# power_cleanup.net
KiCad netlist of a schematic drawn in EAGLE
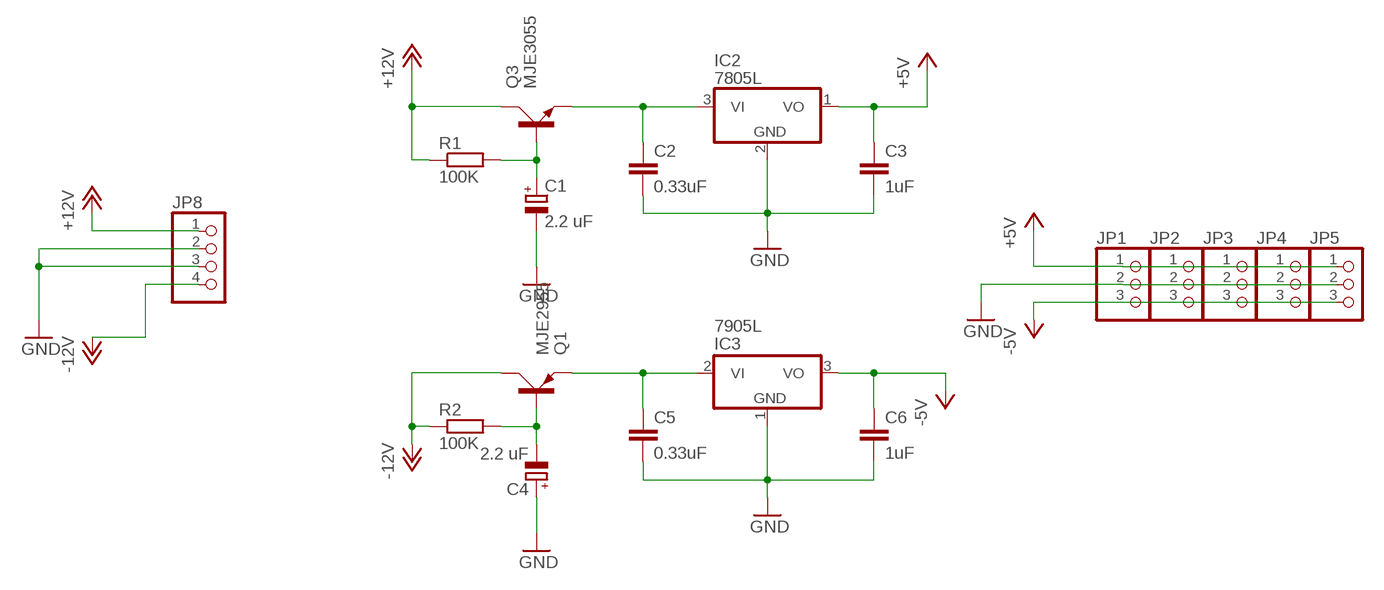
[diagram p0: schematic, sheet 1]

(export (version "E")
  (design (tool "Eeschema 10.0.6"))
  (components
    (comp (ref "C1")
      (value "2.2 uF")
      (footprint "eagle-import:E2-5")
      (libsource (lib "eagle-import") (part "CPOL-EUE2-5"))
    )
    (comp (ref "C2")
      (value "0.33uF")
      (footprint "eagle-import:C025-025X050")
      (libsource (lib "eagle-import") (part "C-EU025-025X050"))
    )
    (comp (ref "C3")
      (value "1uF")
      (footprint "eagle-import:C025-025X050")
      (libsource (lib "eagle-import") (part "C-EU025-025X050"))
    )
    (comp (ref "C4")
      (value "2.2 uF")
      (footprint "eagle-import:E2-5")
      (libsource (lib "eagle-import") (part "CPOL-EUE2-5"))
    )
    (comp (ref "C5")
      (value "0.33uF")
      (footprint "eagle-import:C025-025X050")
      (libsource (lib "eagle-import") (part "C-EU025-025X050"))
    )
    (comp (ref "C6")
      (value "1uF")
      (footprint "eagle-import:C025-025X050")
      (libsource (lib "eagle-import") (part "C-EU025-025X050"))
    )
    (comp (ref "IC2")
      (value "7805L")
      (footprint "eagle-import:TO92")
      (libsource (lib "eagle-import") (part "78L05"))
    )
    (comp (ref "IC3")
      (value "7905L")
      (footprint "eagle-import:TO92")
      (libsource (lib "eagle-import") (part "79L05"))
    )
    (comp (ref "JP1")
      (value "PINHD-1X3")
      (footprint "eagle-import:1X03")
      (libsource (lib "eagle-import") (part "PINHD-1X3"))
    )
    (comp (ref "JP2")
      (value "PINHD-1X3")
      (footprint "eagle-import:1X03")
      (libsource (lib "eagle-import") (part "PINHD-1X3"))
    )
    (comp (ref "JP3")
      (value "PINHD-1X3")
      (footprint "eagle-import:1X03")
      (libsource (lib "eagle-import") (part "PINHD-1X3"))
    )
    (comp (ref "JP4")
      (value "PINHD-1X3")
      (footprint "eagle-import:1X03")
      (libsource (lib "eagle-import") (part "PINHD-1X3"))
    )
    (comp (ref "JP5")
      (value "PINHD-1X3")
      (footprint "eagle-import:1X03")
      (libsource (lib "eagle-import") (part "PINHD-1X3"))
    )
    (comp (ref "JP8")
      (value "PINHD-1X4")
      (footprint "eagle-import:1X04")
      (libsource (lib "eagle-import") (part "PINHD-1X4"))
    )
    (comp (ref "Q1")
      (value "MJE2955")
      (footprint "eagle-import:TO220AV")
      (libsource (lib "eagle-import") (part "MJE2955"))
    )
    (comp (ref "Q3")
      (value "MJE3055")
      (footprint "eagle-import:TO220AV")
      (libsource (lib "eagle-import") (part "MJE3055"))
    )
    (comp (ref "R1")
      (value "100K")
      (footprint "eagle-import:0207_10")
      (libsource (lib "eagle-import") (part "R-EU_0207/10"))
    )
    (comp (ref "R2")
      (value "100K")
      (footprint "eagle-import:0207_10")
      (libsource (lib "eagle-import") (part "R-EU_0207/10"))
    )
  )
  (nets
    (net (code "1") (name "+5V") (class "Default")
      (node (ref "C3") (pin "1") (pinfunction "1_1") (pintype "passive"))
      (node (ref "IC2") (pin "1") (pinfunction "VO_1") (pintype "passive"))
      (node (ref "JP1") (pin "1") (pinfunction "1_1") (pintype "passive"))
      (node (ref "JP2") (pin "1") (pinfunction "1_1") (pintype "passive"))
      (node (ref "JP3") (pin "1") (pinfunction "1_1") (pintype "passive"))
      (node (ref "JP4") (pin "1") (pinfunction "1_1") (pintype "passive"))
      (node (ref "JP5") (pin "1") (pinfunction "1_1") (pintype "passive"))
    )
    (net (code "2") (name "+12V") (class "Default")
      (node (ref "JP8") (pin "1") (pinfunction "1_1") (pintype "passive"))
      (node (ref "Q3") (pin "C") (pinfunction "C_C") (pintype "passive"))
      (node (ref "R1") (pin "1") (pinfunction "1_1") (pintype "passive"))
    )
    (net (code "3") (name "-5V") (class "Default")
      (node (ref "C6") (pin "1") (pinfunction "1_1") (pintype "passive"))
      (node (ref "IC3") (pin "3") (pinfunction "VO_3") (pintype "passive"))
      (node (ref "JP1") (pin "3") (pinfunction "3_3") (pintype "passive"))
      (node (ref "JP2") (pin "3") (pinfunction "3_3") (pintype "passive"))
      (node (ref "JP3") (pin "3") (pinfunction "3_3") (pintype "passive"))
      (node (ref "JP4") (pin "3") (pinfunction "3_3") (pintype "passive"))
      (node (ref "JP5") (pin "3") (pinfunction "3_3") (pintype "passive"))
    )
    (net (code "4") (name "-12V") (class "Default")
      (node (ref "JP8") (pin "4") (pinfunction "4_4") (pintype "passive"))
      (node (ref "Q1") (pin "C") (pinfunction "C_C") (pintype "passive"))
      (node (ref "R2") (pin "1") (pinfunction "1_1") (pintype "passive"))
    )
    (net (code "5") (name "GND") (class "Default")
      (node (ref "C1") (pin "-") (pinfunction "-_-") (pintype "passive"))
      (node (ref "C2") (pin "2") (pinfunction "2_2") (pintype "passive"))
      (node (ref "C3") (pin "2") (pinfunction "2_2") (pintype "passive"))
      (node (ref "C4") (pin "+") (pinfunction "+_+") (pintype "passive"))
      (node (ref "C5") (pin "2") (pinfunction "2_2") (pintype "passive"))
      (node (ref "C6") (pin "2") (pinfunction "2_2") (pintype "passive"))
      (node (ref "IC2") (pin "2") (pinfunction "GND_2") (pintype "passive"))
      (node (ref "IC3") (pin "1") (pinfunction "GND_1") (pintype "passive"))
      (node (ref "JP1") (pin "2") (pinfunction "2_2") (pintype "passive"))
      (node (ref "JP2") (pin "2") (pinfunction "2_2") (pintype "passive"))
      (node (ref "JP3") (pin "2") (pinfunction "2_2") (pintype "passive"))
      (node (ref "JP4") (pin "2") (pinfunction "2_2") (pintype "passive"))
      (node (ref "JP5") (pin "2") (pinfunction "2_2") (pintype "passive"))
      (node (ref "JP8") (pin "2") (pinfunction "2_2") (pintype "passive"))
      (node (ref "JP8") (pin "3") (pinfunction "3_3") (pintype "passive"))
    )
    (net (code "6") (name "Net-(C1-Pad+)") (class "Default")
      (node (ref "C1") (pin "+") (pinfunction "+_+") (pintype "passive"))
      (node (ref "Q3") (pin "B") (pinfunction "B_B") (pintype "passive"))
      (node (ref "R1") (pin "2") (pinfunction "2_2") (pintype "passive"))
    )
    (net (code "7") (name "Net-(C4-Pad-)") (class "Default")
      (node (ref "C4") (pin "-") (pinfunction "-_-") (pintype "passive"))
      (node (ref "Q1") (pin "B") (pinfunction "B_B") (pintype "passive"))
      (node (ref "R2") (pin "2") (pinfunction "2_2") (pintype "passive"))
    )
    (net (code "8") (name "Net-(IC2-VI)") (class "Default")
      (node (ref "C2") (pin "1") (pinfunction "1_1") (pintype "passive"))
      (node (ref "IC2") (pin "3") (pinfunction "VI_3") (pintype "input"))
      (node (ref "Q3") (pin "E") (pinfunction "E_E") (pintype "passive"))
    )
    (net (code "9") (name "Net-(IC3-VI)") (class "Default")
      (node (ref "C5") (pin "1") (pinfunction "1_1") (pintype "passive"))
      (node (ref "IC3") (pin "2") (pinfunction "VI_2") (pintype "input"))
      (node (ref "Q1") (pin "E") (pinfunction "E_E") (pintype "passive"))
    )
  )
)
